# Analog.net
KiCad netlist of a schematic drawn in Altium Designer
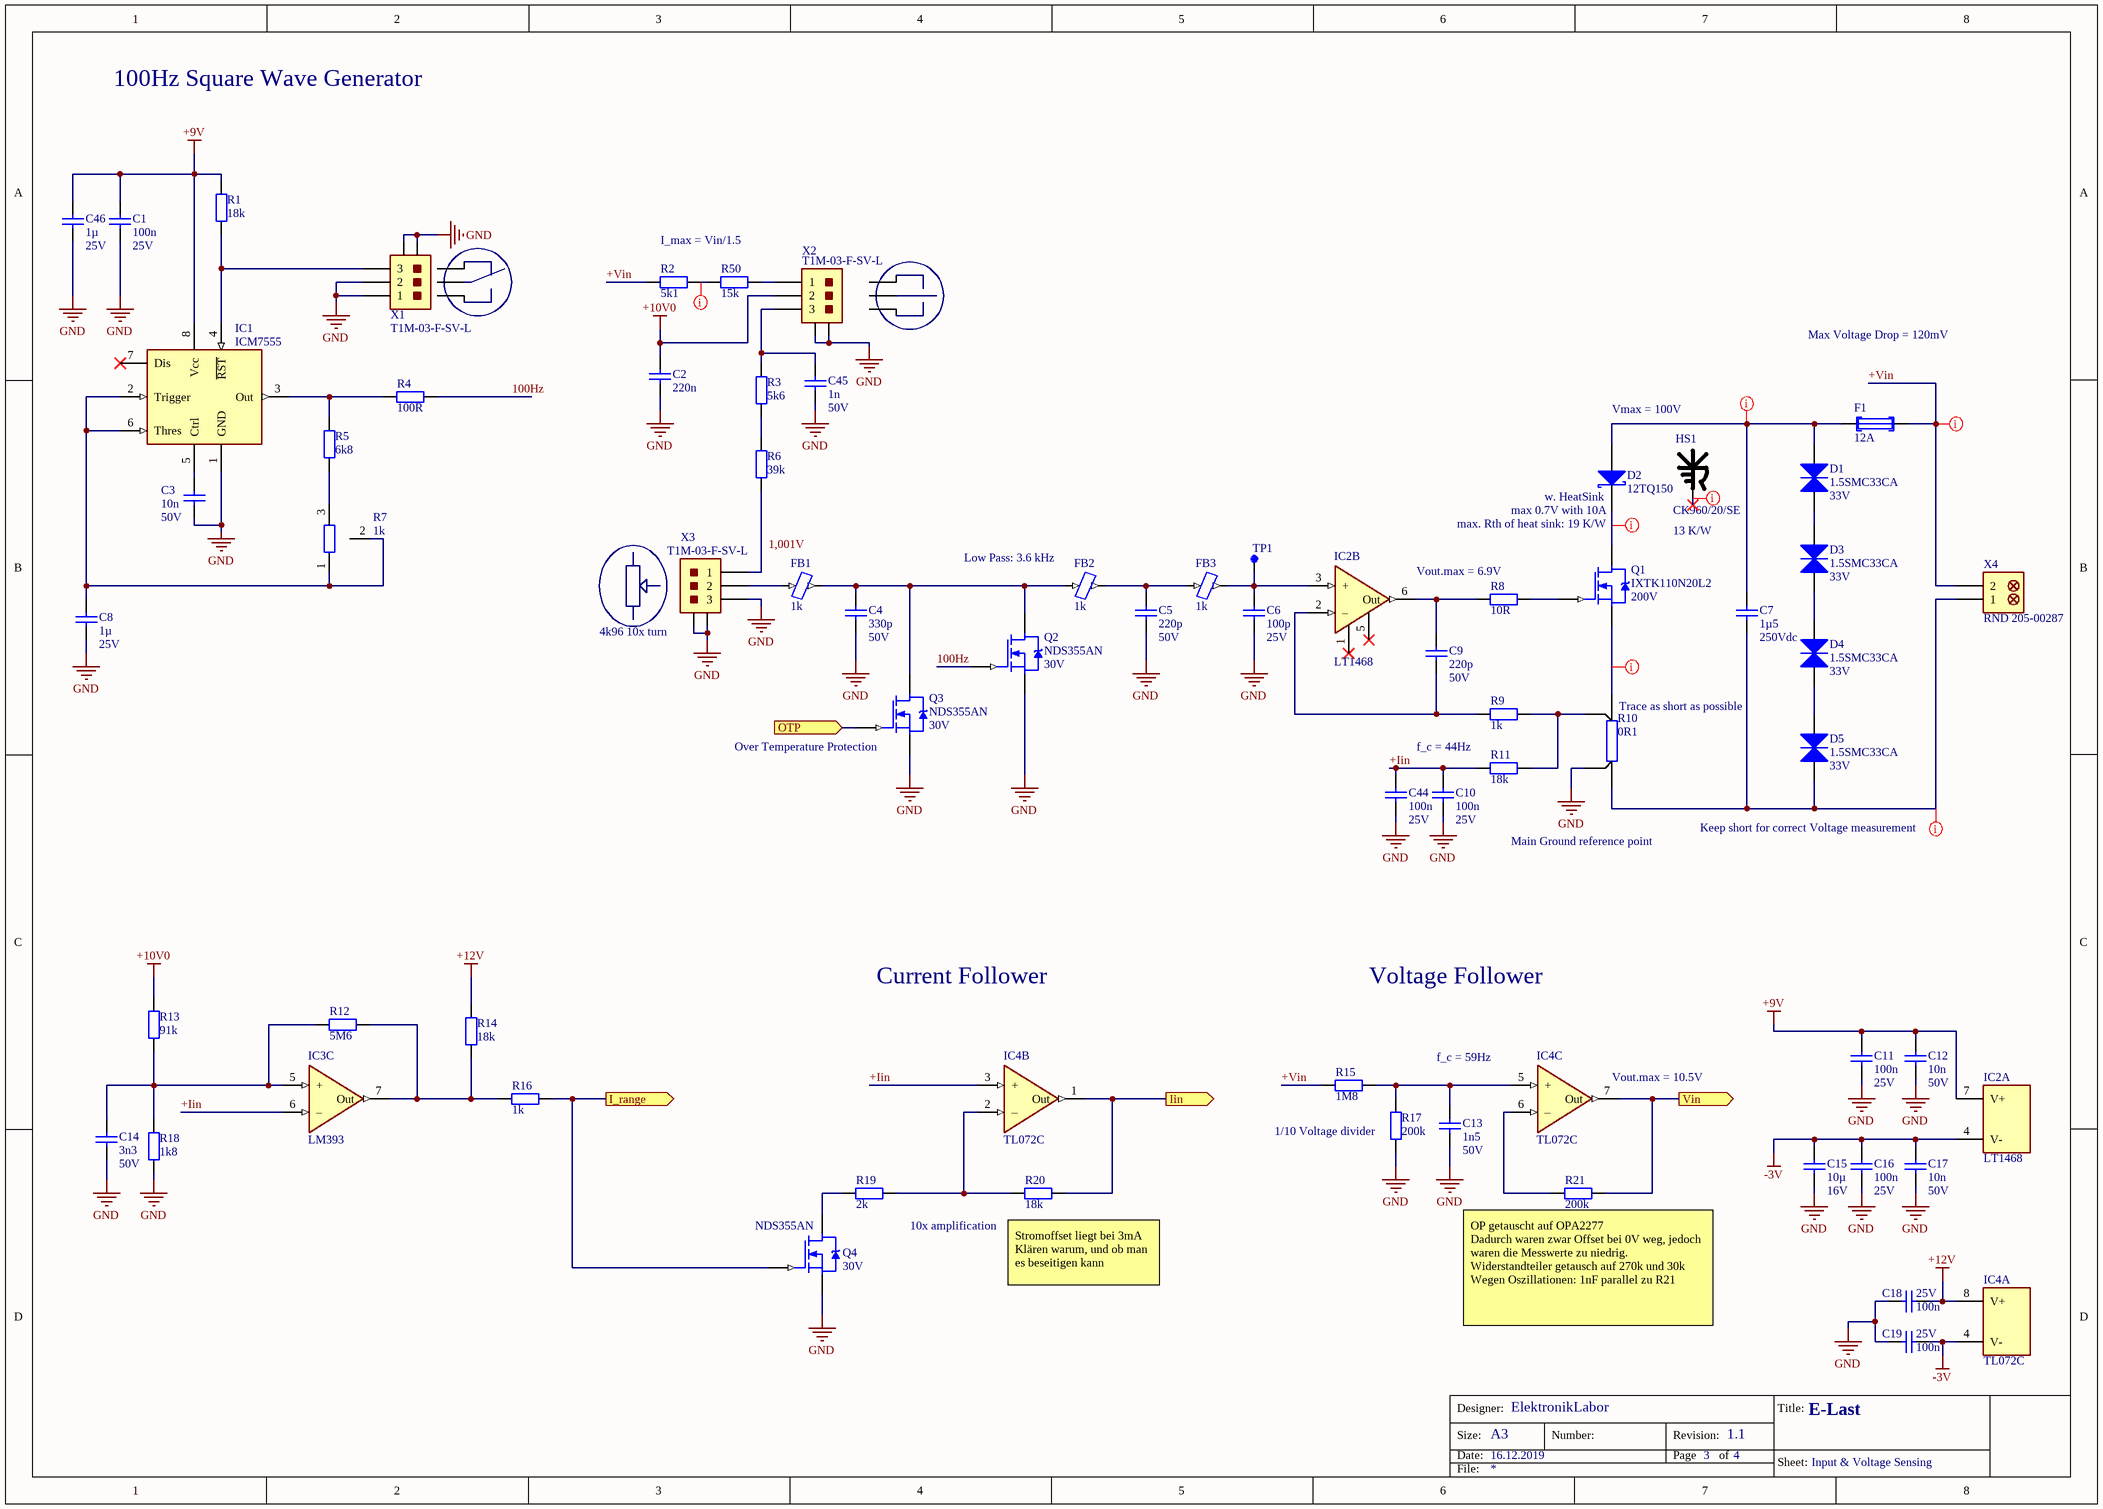
[diagram p0: Analog.SchDoc]

(export (version "E")
  (design (tool "Eeschema 10.0.6"))
  (components
    (comp (ref "C1")
      (value "100n")
      (footprint "C_0805")
      (description "Cap Ceramic 0805 100n 25V")
      (fields (field (name "MANUFACTURER") "generic") (field (name "VOLTAGE") "25V"))
      (libsource (lib "SchLibrary") (part "C-Cer 0805 100n"))
    )
    (comp (ref "C2")
      (value "220n")
      (footprint "C_0805")
      (description "Cap Ceramic 0805 220n 50V")
      (fields (field (name "MANUFACTURER") "generic") (field (name "VOLTAGE") "50V"))
      (libsource (lib "SchLibrary") (part "C-Cer 0805 220n"))
    )
    (comp (ref "C3")
      (value "10n")
      (footprint "C_0805")
      (description "Cap Ceramic 0805 10n 50V")
      (fields (field (name "MANUFACTURER") "generic") (field (name "VOLTAGE") "50V"))
      (libsource (lib "SchLibrary") (part "C-Cer 0805 10n"))
    )
    (comp (ref "C4")
      (value "330p")
      (footprint "C_0805")
      (description "Cap Ceramic 0805 330p 50V")
      (fields (field (name "MANUFACTURER") "generic") (field (name "VOLTAGE") "50V"))
      (libsource (lib "CustomLib") (part "C-Cer 0805 330p"))
    )
    (comp (ref "C5")
      (value "220p")
      (footprint "C_0805")
      (description "Cap Ceramic 0805 220p 50V")
      (fields (field (name "MANUFACTURER") "generic") (field (name "VOLTAGE") "50V"))
      (libsource (lib "CustomLib") (part "C-Cer 0805 220p"))
    )
    (comp (ref "C6")
      (value "100p")
      (footprint "C_0805")
      (description "Cap Ceramic 0805 100p 50V")
      (fields (field (name "MANUFACTURER") "generic") (field (name "VOLTAGE") "25V"))
      (libsource (lib "CustomLib") (part "C-Cer 0805 100p"))
    )
    (comp (ref "C7")
      (value "1µ5")
      (footprint "Cap Film 15mm THT")
      (description "Cap Film 1µ5 250V 15mm")
      (fields
        (field (name "MANUFACTURER") "Panasonic")
        (field (name "PARTNUMBER") "ECQE2155KF")
        (field (name "VOLTAGE") "250Vdc")
      )
      (libsource (lib "CustomLib") (part "Cap-Film 1µ5 250V 15mm"))
    )
    (comp (ref "C8")
      (value "1µ")
      (footprint "C_0805")
      (description "Cap Ceramic 0805 1µ 25V")
      (fields
        (field (name "MANUFACTURER") "Samsung")
        (field (name "PARTNUMBER") "CL21B105KAFNNNE")
        (field (name "VOLTAGE") "25V")
      )
      (libsource (lib "SchLibrary") (part "C-Cer 0805 1µ"))
    )
    (comp (ref "C9")
      (value "220p")
      (footprint "C_0805")
      (description "Cap Ceramic 0805 220p 50V")
      (fields (field (name "MANUFACTURER") "generic") (field (name "VOLTAGE") "50V"))
      (libsource (lib "CustomLib") (part "C-Cer 0805 220p"))
    )
    (comp (ref "C10")
      (value "100n")
      (footprint "C_0805")
      (description "Cap Ceramic 0805 100n 25V")
      (fields (field (name "MANUFACTURER") "generic") (field (name "VOLTAGE") "25V"))
      (libsource (lib "SchLibrary") (part "C-Cer 0805 100n"))
    )
    (comp (ref "C11")
      (value "100n")
      (footprint "C_0805")
      (description "Cap Ceramic 0805 100n 25V")
      (fields (field (name "MANUFACTURER") "generic") (field (name "VOLTAGE") "25V"))
      (libsource (lib "SchLibrary") (part "C-Cer 0805 100n"))
    )
    (comp (ref "C12")
      (value "10n")
      (footprint "C_0805")
      (description "Cap Ceramic 0805 10n 50V")
      (fields (field (name "MANUFACTURER") "generic") (field (name "VOLTAGE") "50V"))
      (libsource (lib "SchLibrary") (part "C-Cer 0805 10n"))
    )
    (comp (ref "C13")
      (value "1n5")
      (footprint "C_0805")
      (description "Cap Ceramic 0805 1n5 50V")
      (fields (field (name "MANUFACTURER") "generic") (field (name "VOLTAGE") "50V"))
      (libsource (lib "CustomLib") (part "C-Cer 0805 1n5"))
    )
    (comp (ref "C14")
      (value "3n3")
      (footprint "C_0805")
      (description "Cap Ceramic 0805 3n3 50V")
      (fields (field (name "MANUFACTURER") "generic") (field (name "VOLTAGE") "50V"))
      (libsource (lib "CustomLib") (part "C-Cer 0805 3n3"))
    )
    (comp (ref "C15")
      (value "10µ")
      (footprint "C_1206")
      (description "Cap Ceramic 1206 10µ 16V")
      (fields
        (field (name "PARTNUMBER") "CL31B106MOHNNNE")
        (field (name "MANUFACTURER") "Samsung")
        (field (name "VOLTAGE") "16V")
      )
      (libsource (lib "CustomLib") (part "C-Cer 1206 16V 10µ"))
    )
    (comp (ref "C16")
      (value "100n")
      (footprint "C_0805")
      (description "Cap Ceramic 0805 100n 25V")
      (fields (field (name "MANUFACTURER") "generic") (field (name "VOLTAGE") "25V"))
      (libsource (lib "SchLibrary") (part "C-Cer 0805 100n"))
    )
    (comp (ref "C17")
      (value "10n")
      (footprint "C_0805")
      (description "Cap Ceramic 0805 10n 50V")
      (fields (field (name "MANUFACTURER") "generic") (field (name "VOLTAGE") "50V"))
      (libsource (lib "SchLibrary") (part "C-Cer 0805 10n"))
    )
    (comp (ref "C18")
      (value "100n")
      (footprint "C_0805")
      (description "Cap Ceramic 0805 100n 25V")
      (fields (field (name "MANUFACTURER") "generic") (field (name "VOLTAGE") "25V"))
      (libsource (lib "SchLibrary") (part "C-Cer 0805 100n"))
    )
    (comp (ref "C19")
      (value "100n")
      (footprint "C_0805")
      (description "Cap Ceramic 0805 100n 25V")
      (fields (field (name "MANUFACTURER") "generic") (field (name "VOLTAGE") "25V"))
      (libsource (lib "SchLibrary") (part "C-Cer 0805 100n"))
    )
    (comp (ref "C44")
      (value "100n")
      (footprint "C_0805")
      (description "Cap Ceramic 0805 100n 25V")
      (fields (field (name "MANUFACTURER") "generic") (field (name "VOLTAGE") "25V"))
      (libsource (lib "SchLibrary") (part "C-Cer 0805 100n"))
    )
    (comp (ref "C45")
      (value "1n")
      (footprint "C_0805")
      (description "Cap Ceramic 0805 1n 50V")
      (fields (field (name "MANUFACTURER") "generic") (field (name "VOLTAGE") "50V"))
      (libsource (lib "CustomLib") (part "C-Cer 0805 1n"))
    )
    (comp (ref "C46")
      (value "1µ")
      (footprint "C_0805")
      (description "Cap Ceramic 0805 1µ 25V")
      (fields
        (field (name "MANUFACTURER") "Samsung")
        (field (name "PARTNUMBER") "CL21B105KAFNNNE")
        (field (name "VOLTAGE") "25V")
      )
      (libsource (lib "SchLibrary") (part "C-Cer 0805 1µ"))
    )
    (comp (ref "D1")
      (value "1.5SMC33CA")
      (footprint "DO-214AB")
      (description "Diode, TVS, Bi, 33V, 33A, DO-214AB")
      (fields
        (field (name "MANUFACTURER") "Littelfuse")
        (field (name "VOLTAGE") "33V")
        (field (name "COMPONENTLINK1URL") "G:\\Daten\\Datenblätter\\Dioden\\1_5SMC_TVS.pdf")
      )
      (libsource (lib "CustomLib") (part "Diode 1.5SMC33CA"))
    )
    (comp (ref "D2")
      (value "12TQ150")
      (footprint "TO-220-2 Vertical")
      (description "Diode Schottky, 150V, 15A, TO-220-2")
      (fields
        (field (name "MANUFACTURER") "SMC")
        (field (name "VOLTAGE") "150V")
        (field (name "COMPONENTLINK1URL") "G:\\Daten\\Datenblätter\\Dioden\\12TQ150.pdf")
      )
      (libsource (lib "SchLibrary") (part "Diode Schottky 15A"))
    )
    (comp (ref "D3")
      (value "1.5SMC33CA")
      (footprint "DO-214AB")
      (description "Diode, TVS, Bi, 33V, 33A, DO-214AB")
      (fields
        (field (name "MANUFACTURER") "Littelfuse")
        (field (name "VOLTAGE") "33V")
        (field (name "COMPONENTLINK1URL") "G:\\Daten\\Datenblätter\\Dioden\\1_5SMC_TVS.pdf")
      )
      (libsource (lib "CustomLib") (part "Diode 1.5SMC33CA"))
    )
    (comp (ref "D4")
      (value "1.5SMC33CA")
      (footprint "DO-214AB")
      (description "Diode, TVS, Bi, 33V, 33A, DO-214AB")
      (fields
        (field (name "MANUFACTURER") "Littelfuse")
        (field (name "VOLTAGE") "33V")
        (field (name "COMPONENTLINK1URL") "G:\\Daten\\Datenblätter\\Dioden\\1_5SMC_TVS.pdf")
      )
      (libsource (lib "CustomLib") (part "Diode 1.5SMC33CA"))
    )
    (comp (ref "D5")
      (value "1.5SMC33CA")
      (footprint "DO-214AB")
      (description "Diode, TVS, Bi, 33V, 33A, DO-214AB")
      (fields
        (field (name "MANUFACTURER") "Littelfuse")
        (field (name "VOLTAGE") "33V")
        (field (name "COMPONENTLINK1URL") "G:\\Daten\\Datenblätter\\Dioden\\1_5SMC_TVS.pdf")
      )
      (libsource (lib "CustomLib") (part "Diode 1.5SMC33CA"))
    )
    (comp (ref "F1")
      (value "12A")
      (footprint "Fuse w Holder 5x20mm 25mm")
      (description "Fuse w Holder 5x20mm 25mm 12A THT")
      (fields
        (field (name "MANUFACTURER") "Schurter")
        (field (name "PARTNUMBER") "0031.8211")
        (field (name "COMPONENTLINK1URL") "G:\\Daten\\Datenblätter\\Sicherungen\\Halter_15x20mm_Schurter_0031.82x1.pdf")
      )
      (libsource (lib "SchLibrary") (part "Fuse w Holder 0031.8211 12A"))
    )
    (comp (ref "FB1")
      (value "1k")
      (footprint "Ferrite 0805")
      (description "Ferrite Bead 0805 1k 100MHz")
      (fields
        (field (name "MANUFACTURER") "Murata")
        (field (name "PARTNUMBER") "BLM21AG102SN1")
        (field (name "COMPONENTLINK1URL") "G:\\Daten\\Datenblätter\\Ferrite\\BLM21AG102SN1.pdf")
      )
      (libsource (lib "SchLibrary") (part "Ferrite Bead BLM21AG102SN1"))
    )
    (comp (ref "FB2")
      (value "1k")
      (footprint "Ferrite 0805")
      (description "Ferrite Bead 0805 1k 100MHz")
      (fields
        (field (name "MANUFACTURER") "Murata")
        (field (name "PARTNUMBER") "BLM21AG102SN1")
        (field (name "COMPONENTLINK1URL") "G:\\Daten\\Datenblätter\\Ferrite\\BLM21AG102SN1.pdf")
      )
      (libsource (lib "SchLibrary") (part "Ferrite Bead BLM21AG102SN1"))
    )
    (comp (ref "FB3")
      (value "1k")
      (footprint "Ferrite 0805")
      (description "Ferrite Bead 0805 1k 100MHz")
      (fields
        (field (name "MANUFACTURER") "Murata")
        (field (name "PARTNUMBER") "BLM21AG102SN1")
        (field (name "COMPONENTLINK1URL") "G:\\Daten\\Datenblätter\\Ferrite\\BLM21AG102SN1.pdf")
      )
      (libsource (lib "SchLibrary") (part "Ferrite Bead BLM21AG102SN1"))
    )
    (comp (ref "HS1")
      (value "CK960/20/SE")
      (footprint "Mech Heat Sink CK960/20/SE")
      (description "Mech Heat Sink CK960/20/SE TO-220; Unfertig")
      (fields
        (field (name "MANUFACTURER") "Alutronic")
        (field (name "COMPONENTLINK1URL") "G:\\Daten\\Datenblätter\\Kühlkörper\\CK960-20-SE.pdf")
      )
      (libsource (lib "CustomLib") (part "Mech Heat Sink CK960/20/SE"))
    )
    (comp (ref "IC1")
      (value "ICM7555")
      (footprint "SOIC8_N")
      (description "Timer ICM7555 8-SOIC")
      (fields
        (field (name "MANUFACTURER") "Intersil")
        (field (name "PARTNUMBER") "ICM7555IBA")
        (field (name "COMPONENTLINK1URL") "G:\\Daten\\Datenblätter\\Timer\\ICM755IBA.pdf")
      )
      (libsource (lib "CustomLib") (part "Timer ICM7555IBA"))
    )
    (comp (ref "IC2")
      (value "LT1468")
      (footprint "SOIC8_N")
      (description "OpAmp LT1468 1x 90MHz")
      (fields
        (field (name "MANUFACTURER") "Linear Technology")
        (field (name "PARTNUMBER") "LT1468CS8")
        (field (name "COMPONENTLINK1URL") "G:\\Daten\\Datenblätter\\Operationsverstärker\\LT1468.pdf")
      )
      (libsource (lib "SchLibrary") (part "LT1468"))
    )
    (comp (ref "IC3")
      (value "LM393")
      (footprint "SOIC8_N")
      (description "Comparator LM393DT 2x")
      (fields
        (field (name "MANUFACTURER") "ST")
        (field (name "PARTNUMBER") "LM393DT")
        (field (name "COMPONENTLINK1URL") "G:\\Daten\\Datenblätter\\Komparatoren\\ST_LM393.pdf")
      )
      (libsource (lib "SchLibrary") (part "LM393DT"))
    )
    (comp (ref "IC4")
      (value "TL072C")
      (footprint "SOIC8_N")
      (description "OpAmp TL072CD 2x JFET 3MHz")
      (fields
        (field (name "MANUFACTURER") "Texas Instruments")
        (field (name "PARTNUMBER") "TL072CD")
        (field (name "COMPONENTLINK1URL") "G:\\Daten\\Datenblätter\\Operationsverstärker\\TL072C.pdf")
      )
      (libsource (lib "SchLibrary") (part "TL072C"))
    )
    (comp (ref "Q1")
      (value "IXTK110N20L2")
      (footprint "TO-264-3 vertical")
      (description "Transistor n-MOS, TO-264, 200V, THT")
      (fields
        (field (name "MANUFACTURER") "IXYS")
        (field (name "VOLTAGE") "200V")
        (field (name "COMPONENTLINK1URL") "G:\\Daten\\Datenblätter\\Transistoren\\nMOS_IXTK110N20L2.pdf")
      )
      (libsource (lib "SchLibrary") (part "Transistor n-MOS IXTK110N20L2"))
    )
    (comp (ref "Q2")
      (value "NDS355AN")
      (footprint "SOT23_N - n-MOS")
      (description "Transistor n-MOS SOT-23 30V Vgs=20V")
      (fields
        (field (name "MANUFACTURER") "ON Semiconductor")
        (field (name "VOLTAGE") "30V")
        (field (name "COMPONENTLINK1URL") "G:\\Daten\\Datenblätter\\Transistoren\\nMOS_NDS355AN.pdf")
      )
      (libsource (lib "CustomLib") (part "Transistor n-MOS NDS355AN"))
    )
    (comp (ref "Q3")
      (value "NDS355AN")
      (footprint "SOT23_N - n-MOS")
      (description "Transistor n-MOS SOT-23 30V Vgs=20V")
      (fields
        (field (name "MANUFACTURER") "ON Semiconductor")
        (field (name "VOLTAGE") "30V")
        (field (name "COMPONENTLINK1URL") "G:\\Daten\\Datenblätter\\Transistoren\\nMOS_NDS355AN.pdf")
      )
      (libsource (lib "CustomLib") (part "Transistor n-MOS NDS355AN"))
    )
    (comp (ref "Q4")
      (value "NDS355AN")
      (footprint "SOT23_N - n-MOS")
      (description "Transistor n-MOS SOT-23 30V Vgs=20V")
      (fields
        (field (name "MANUFACTURER") "ON Semiconductor")
        (field (name "VOLTAGE") "30V")
        (field (name "COMPONENTLINK1URL") "G:\\Daten\\Datenblätter\\Transistoren\\nMOS_NDS355AN.pdf")
      )
      (libsource (lib "SchLibrary") (part "Transistor n-MOS NDS355AN"))
    )
    (comp (ref "R1")
      (value "18k")
      (footprint "Res 0805")
      (description "Resistor 0805 18k")
      (fields (field (name "MANUFACTURER") "generic") (field (name "POWER") "0.125W"))
      (libsource (lib "CustomLib") (part "Res 0805 18k"))
    )
    (comp (ref "R2")
      (value "5k1")
      (footprint "Res 0805")
      (description "Resistor 0805 5k1")
      (fields (field (name "MANUFACTURER") "generic") (field (name "POWER") "0.125W"))
      (libsource (lib "CustomLib") (part "Res 0805 5k1"))
    )
    (comp (ref "R3")
      (value "5k6")
      (footprint "Res 0805")
      (description "Resistor 0805 5k6")
      (fields (field (name "MANUFACTURER") "generic") (field (name "POWER") "0.125W"))
      (libsource (lib "CustomLib") (part "Res 0805 5k6"))
    )
    (comp (ref "R4")
      (value "100R")
      (footprint "Res 0805")
      (description "Resistor 0805 100R")
      (fields (field (name "MANUFACTURER") "generic") (field (name "POWER") "0.125W"))
      (libsource (lib "SchLibrary") (part "Res 0805 100R"))
    )
    (comp (ref "R5")
      (value "6k8")
      (footprint "Res 0805")
      (description "Resistor 0805 6k8")
      (fields (field (name "MANUFACTURER") "generic") (field (name "POWER") "0.125W"))
      (libsource (lib "SchLibrary") (part "Res 0805 6k8"))
    )
    (comp (ref "R6")
      (value "39k")
      (footprint "Res 0805")
      (description "Resistor 0805 39k")
      (fields (field (name "MANUFACTURER") "generic") (field (name "POWER") "0.125W"))
      (libsource (lib "CustomLib") (part "Res 0805 39k"))
    )
    (comp (ref "R7")
      (value "1k")
      (footprint "Poti 3296Y")
      (description "Pot 1k THT 30 turns")
      (fields
        (field (name "MANUFACTURER") "Suntan")
        (field (name "PARTNUMBER") "TSR-3296-Y-102-R")
        (field (name "COMPONENTLINK1URL") "G:\\Daten\\Datenblätter\\Potentiometer\\TSR-3296.pdf")
      )
      (libsource (lib "SchLibrary") (part "Pot 1k THT"))
    )
    (comp (ref "R8")
      (value "10R")
      (footprint "Res 0805")
      (description "Resistor 0805 10R")
      (fields (field (name "MANUFACTURER") "generic") (field (name "POWER") "0.125W"))
      (libsource (lib "SchLibrary") (part "Res 0805 10R"))
    )
    (comp (ref "R9")
      (value "1k")
      (footprint "Res 0805")
      (description "Resistor 0805 1k")
      (fields (field (name "MANUFACTURER") "generic") (field (name "POWER") "0.125W"))
      (libsource (lib "SchLibrary") (part "Res 0805 1k"))
    )
    (comp (ref "R10")
      (value "0R1")
      (footprint "Res 4-SIL")
      (description "Resistor 4-SIL 0R1 0.5% 40W")
      (fields
        (field (name "MANUFACTURER") "Riedon")
        (field (name "PARTNUMBER") "PCS-0R1D1")
        (field (name "COMPONENTLINK1URL") "G:\\Daten\\Datenblätter\\Widerstände\\Riedon_PCS-PBV.pdf")
      )
      (libsource (lib "SchLibrary") (part "Res 4-SIL 0R1"))
    )
    (comp (ref "R11")
      (value "18k")
      (footprint "Res 0805")
      (description "Resistor 0805 18k")
      (fields (field (name "MANUFACTURER") "generic") (field (name "POWER") "0.125W"))
      (libsource (lib "") (part "Res 0805 18k_1"))
    )
    (comp (ref "R12")
      (value "5M6")
      (footprint "Res 0805")
      (description "Resistor 0805 5M6")
      (fields (field (name "MANUFACTURER") "generic") (field (name "POWER") "0.125W"))
      (libsource (lib "SchLibrary") (part "Res 0805 5M6"))
    )
    (comp (ref "R13")
      (value "91k")
      (footprint "Res 0805")
      (description "Resistor 0805 91k")
      (fields (field (name "MANUFACTURER") "generic") (field (name "POWER") "0.125W"))
      (libsource (lib "SchLibrary") (part "Res 0805 91k"))
    )
    (comp (ref "R14")
      (value "18k")
      (footprint "Res 0805")
      (description "Resistor 0805 18k")
      (fields (field (name "MANUFACTURER") "generic") (field (name "POWER") "0.125W"))
      (libsource (lib "SchLibrary") (part "Res 0805 18k"))
    )
    (comp (ref "R15")
      (value "1M8")
      (footprint "Res 0805")
      (description "Resistor 0805 1M8")
      (fields (field (name "MANUFACTURER") "generic") (field (name "POWER") "0.125W"))
      (libsource (lib "SchLibrary") (part "Res 0805 1M8"))
    )
    (comp (ref "R16")
      (value "1k")
      (footprint "Res 0805")
      (description "Resistor 0805 1k")
      (fields (field (name "MANUFACTURER") "generic") (field (name "POWER") "0.125W"))
      (libsource (lib "SchLibrary") (part "Res 0805 1k"))
    )
    (comp (ref "R17")
      (value "200k")
      (footprint "Res 0805")
      (description "Resistor 0805 200k")
      (fields (field (name "MANUFACTURER") "generic") (field (name "POWER") "0.125W"))
      (libsource (lib "") (part "Res 0805 200k_1"))
    )
    (comp (ref "R18")
      (value "1k8")
      (footprint "Res 0805")
      (description "Resistor 0805 1k8")
      (fields (field (name "MANUFACTURER") "generic") (field (name "POWER") "0.125W"))
      (libsource (lib "SchLibrary") (part "Res 0805 1k8"))
    )
    (comp (ref "R19")
      (value "2k")
      (footprint "Res 0805")
      (description "Resistor 0805 2k")
      (fields (field (name "MANUFACTURER") "generic") (field (name "POWER") "0.125W"))
      (libsource (lib "SchLibrary") (part "Res 0805 2k"))
    )
    (comp (ref "R20")
      (value "18k")
      (footprint "Res 0805")
      (description "Resistor 0805 18k")
      (fields (field (name "MANUFACTURER") "generic") (field (name "POWER") "0.125W"))
      (libsource (lib "") (part "Res 0805 18k_1"))
    )
    (comp (ref "R21")
      (value "200k")
      (footprint "Res 0805")
      (description "Resistor 0805 200k")
      (fields (field (name "MANUFACTURER") "generic") (field (name "POWER") "0.125W"))
      (libsource (lib "SchLibrary") (part "Res 0805 200k"))
    )
    (comp (ref "R50")
      (value "15k")
      (footprint "Res 0805")
      (description "Resistor 0805 15k")
      (fields (field (name "MANUFACTURER") "generic") (field (name "POWER") "0.125W"))
      (libsource (lib "CustomLib") (part "Res 0805 15k"))
    )
    (comp (ref "TP1")
      (value "*")
      (footprint "Test Point SMD Rnd 1mm")
      (description "Test Point")
      (libsource (lib "CustomLib") (part "Test Point"))
    )
    (comp (ref "X1")
      (value "T1M-03-F-SV-L")
      (footprint "T1M-03-XX-S-V")
      (description "Connector, Male, Vertical, 3-Pin, 1mm, SMD")
      (fields
        (field (name "MANUFACTURER") "SAMTEC")
        (field (name "MATINGPARTNUMBER") "S1SS-03-L")
        (field (name "COMPONENTLINK1URL") "G:\\Daten\\Datenblätter\\Steckverbinder\\T1M-Single-Row.pdf")
      )
      (libsource (lib "") (part "Con Male 3-Pin_2"))
    )
    (comp (ref "X2")
      (value "T1M-03-F-SV-L")
      (footprint "T1M-03-XX-S-V")
      (description "Connector, Male, Vertical, 3-Pin, 1mm, SMD")
      (fields
        (field (name "MANUFACTURER") "SAMTEC")
        (field (name "MATINGPARTNUMBER") "S1SS-03-L")
        (field (name "COMPONENTLINK1URL") "G:\\Daten\\Datenblätter\\Steckverbinder\\T1M-Single-Row.pdf")
      )
      (libsource (lib "SchLibrary") (part "Con Male 3-Pin"))
    )
    (comp (ref "X3")
      (value "T1M-03-F-SV-L")
      (footprint "T1M-03-XX-S-V")
      (description "Connector, Male, Vertical, 3-Pin, 1mm, SMD")
      (fields
        (field (name "MANUFACTURER") "SAMTEC")
        (field (name "MATINGPARTNUMBER") "S1SS-03-L")
        (field (name "COMPONENTLINK1URL") "G:\\Daten\\Datenblätter\\Steckverbinder\\T1M-Single-Row.pdf")
      )
      (libsource (lib "") (part "Con Male 3-Pin_1"))
    )
    (comp (ref "X4")
      (value "RND 205-00287")
      (footprint "TRMNL 5.08mm 2x")
      (description "Terminal, 2-Pin, 5.08mm, THT")
      (fields
        (field (name "MANUFACTURER") "RND connect")
        (field (name "COMPONENTLINK2URL") "G:\\Daten\\Datenblätter\\Verbinder\\Terminal_RND_205-00287.pdf")
      )
      (libsource (lib "SchLibrary") (part "Termial 2pin 5.08mm"))
    )
  )
  (nets
    (net (code "1") (name "+9V") (class "Default")
      (node (ref "C1") (pin "1") (pinfunction "1_1") (pintype "passive"))
      (node (ref "C11") (pin "1") (pinfunction "1_1") (pintype "passive"))
      (node (ref "C12") (pin "1") (pinfunction "1_1") (pintype "passive"))
      (node (ref "C46") (pin "1") (pinfunction "1_1") (pintype "passive"))
      (node (ref "IC1") (pin "8") (pinfunction "Vcc_8") (pintype "power_in"))
      (node (ref "IC2") (pin "7") (pinfunction "V+_7") (pintype "power_in"))
      (node (ref "R1") (pin "1") (pinfunction "1_1") (pintype "passive"))
    )
    (net (code "2") (name "+10V0") (class "Default")
      (node (ref "C2") (pin "1") (pinfunction "1_1") (pintype "passive"))
      (node (ref "R13") (pin "1") (pinfunction "1_1") (pintype "passive"))
      (node (ref "X2") (pin "2") (pinfunction "2_2") (pintype "passive"))
    )
    (net (code "3") (name "+12V") (class "Default")
      (node (ref "C18") (pin "2") (pinfunction "2_2") (pintype "passive"))
      (node (ref "IC4") (pin "8") (pinfunction "V+_8") (pintype "power_in"))
      (node (ref "R14") (pin "1") (pinfunction "1_1") (pintype "passive"))
    )
    (net (code "4") (name "-3V") (class "Default")
      (node (ref "C15") (pin "1") (pinfunction "1_1") (pintype "passive"))
      (node (ref "C16") (pin "1") (pinfunction "1_1") (pintype "passive"))
      (node (ref "C17") (pin "1") (pinfunction "1_1") (pintype "passive"))
      (node (ref "C19") (pin "1") (pinfunction "1_1") (pintype "passive"))
      (node (ref "IC2") (pin "4") (pinfunction "V-_4") (pintype "power_in"))
      (node (ref "IC4") (pin "4") (pinfunction "V-_4") (pintype "power_in"))
    )
    (net (code "5") (name "/+Iin") (class "Default")
      (node (ref "C10") (pin "1") (pinfunction "1_1") (pintype "passive"))
      (node (ref "C44") (pin "1") (pinfunction "1_1") (pintype "passive"))
      (node (ref "IC3") (pin "6") (pinfunction "–_6") (pintype "input"))
      (node (ref "IC4") (pin "3") (pinfunction "+_3") (pintype "input"))
      (node (ref "R11") (pin "1") (pinfunction "1_1") (pintype "passive"))
    )
    (net (code "6") (name "/+Vin") (class "Default")
      (node (ref "F1") (pin "2") (pinfunction "2_2") (pintype "passive"))
      (node (ref "R15") (pin "1") (pinfunction "1_1") (pintype "passive"))
      (node (ref "R2") (pin "1") (pinfunction "1_1") (pintype "passive"))
      (node (ref "X4") (pin "2") (pinfunction "2_2") (pintype "passive"))
    )
    (net (code "7") (name "/100Hz") (class "Default")
      (node (ref "Q2") (pin "1") (pinfunction "G_1") (pintype "input"))
      (node (ref "R4") (pin "2") (pinfunction "2_2") (pintype "passive"))
    )
    (net (code "8") (name "/I_range") (class "Default")
      (node (ref "Q4") (pin "1") (pinfunction "G_1") (pintype "input"))
      (node (ref "R16") (pin "2") (pinfunction "2_2") (pintype "passive"))
    )
    (net (code "9") (name "/Iin") (class "Default")
      (node (ref "IC4") (pin "1") (pinfunction "Out_1") (pintype "output"))
      (node (ref "R20") (pin "2") (pinfunction "2_2") (pintype "passive"))
    )
    (net (code "10") (name "/OTP") (class "Default")
      (node (ref "Q3") (pin "1") (pinfunction "G_1") (pintype "input"))
    )
    (net (code "11") (name "/Vin") (class "Default")
      (node (ref "IC4") (pin "7") (pinfunction "Out_7") (pintype "output"))
      (node (ref "R21") (pin "2") (pinfunction "2_2") (pintype "passive"))
    )
    (net (code "12") (name "GND") (class "Default")
      (node (ref "C1") (pin "2") (pinfunction "2_2") (pintype "passive"))
      (node (ref "C10") (pin "2") (pinfunction "2_2") (pintype "passive"))
      (node (ref "C11") (pin "2") (pinfunction "2_2") (pintype "passive"))
      (node (ref "C12") (pin "2") (pinfunction "2_2") (pintype "passive"))
      (node (ref "C13") (pin "2") (pinfunction "2_2") (pintype "passive"))
      (node (ref "C14") (pin "2") (pinfunction "2_2") (pintype "passive"))
      (node (ref "C15") (pin "2") (pinfunction "2_2") (pintype "passive"))
      (node (ref "C16") (pin "2") (pinfunction "2_2") (pintype "passive"))
      (node (ref "C17") (pin "2") (pinfunction "2_2") (pintype "passive"))
      (node (ref "C18") (pin "1") (pinfunction "1_1") (pintype "passive"))
      (node (ref "C19") (pin "2") (pinfunction "2_2") (pintype "passive"))
      (node (ref "C2") (pin "2") (pinfunction "2_2") (pintype "passive"))
      (node (ref "C3") (pin "2") (pinfunction "2_2") (pintype "passive"))
      (node (ref "C4") (pin "2") (pinfunction "2_2") (pintype "passive"))
      (node (ref "C44") (pin "2") (pinfunction "2_2") (pintype "passive"))
      (node (ref "C45") (pin "2") (pinfunction "2_2") (pintype "passive"))
      (node (ref "C46") (pin "2") (pinfunction "2_2") (pintype "passive"))
      (node (ref "C5") (pin "2") (pinfunction "2_2") (pintype "passive"))
      (node (ref "C6") (pin "2") (pinfunction "2_2") (pintype "passive"))
      (node (ref "C8") (pin "2") (pinfunction "2_2") (pintype "passive"))
      (node (ref "IC1") (pin "1") (pinfunction "GND_1") (pintype "passive"))
      (node (ref "Q2") (pin "2") (pinfunction "S_2") (pintype "passive"))
      (node (ref "Q3") (pin "2") (pinfunction "S_2") (pintype "passive"))
      (node (ref "Q4") (pin "2") (pinfunction "S_2") (pintype "passive"))
      (node (ref "R10") (pin "3") (pinfunction "3_3") (pintype "passive"))
      (node (ref "R17") (pin "2") (pinfunction "2_2") (pintype "passive"))
      (node (ref "R18") (pin "2") (pinfunction "2_2") (pintype "passive"))
      (node (ref "X1") (pin "1") (pinfunction "1_1") (pintype "passive"))
      (node (ref "X1") (pin "2") (pinfunction "2_2") (pintype "passive"))
      (node (ref "X1") (pin "4") (pinfunction "CASE_4") (pintype "passive"))
      (node (ref "X1") (pin "5") (pinfunction "CASE_5") (pintype "passive"))
      (node (ref "X2") (pin "4") (pinfunction "CASE_4") (pintype "passive"))
      (node (ref "X2") (pin "5") (pinfunction "CASE_5") (pintype "passive"))
      (node (ref "X3") (pin "3") (pinfunction "3_3") (pintype "passive"))
      (node (ref "X3") (pin "4") (pinfunction "CASE_4") (pintype "passive"))
      (node (ref "X3") (pin "5") (pinfunction "CASE_5") (pintype "passive"))
    )
    (net (code "13") (name "Net-(C5-Pad1)") (class "Default")
      (node (ref "C5") (pin "1") (pinfunction "1_1") (pintype "passive"))
      (node (ref "FB2") (pin "2") (pinfunction "2_2") (pintype "output"))
      (node (ref "FB3") (pin "1") (pinfunction "1_1") (pintype "input"))
    )
    (net (code "14") (name "Net-(C7-Pad2)") (class "Default")
      (node (ref "C7") (pin "2") (pinfunction "2_2") (pintype "passive"))
      (node (ref "D5") (pin "2") (pinfunction "2_2") (pintype "passive"))
      (node (ref "R10") (pin "4") (pinfunction "4_4") (pintype "passive"))
      (node (ref "X4") (pin "1") (pinfunction "1_1") (pintype "passive"))
    )
    (net (code "15") (name "Net-(C45-Pad1)") (class "Default")
      (node (ref "C45") (pin "1") (pinfunction "1_1") (pintype "passive"))
      (node (ref "R3") (pin "1") (pinfunction "1_1") (pintype "passive"))
      (node (ref "X2") (pin "3") (pinfunction "3_3") (pintype "passive"))
    )
    (net (code "16") (name "Net-(D1-Pad2)") (class "Default")
      (node (ref "D1") (pin "2") (pinfunction "2_2") (pintype "passive"))
      (node (ref "D3") (pin "1") (pinfunction "1_1") (pintype "passive"))
    )
    (net (code "17") (name "Net-(D2-A)") (class "Default")
      (node (ref "C7") (pin "1") (pinfunction "1_1") (pintype "passive"))
      (node (ref "D1") (pin "1") (pinfunction "1_1") (pintype "passive"))
      (node (ref "D2") (pin "2") (pinfunction "A_2") (pintype "passive"))
      (node (ref "F1") (pin "1") (pinfunction "1_1") (pintype "passive"))
    )
    (net (code "18") (name "Net-(D2-K)") (class "Default")
      (node (ref "D2") (pin "1") (pinfunction "K_1") (pintype "passive"))
      (node (ref "Q1") (pin "2") (pinfunction "D_2") (pintype "passive"))
    )
    (net (code "19") (name "Net-(D3-Pad2)") (class "Default")
      (node (ref "D3") (pin "2") (pinfunction "2_2") (pintype "passive"))
      (node (ref "D4") (pin "1") (pinfunction "1_1") (pintype "passive"))
    )
    (net (code "20") (name "Net-(D4-Pad2)") (class "Default")
      (node (ref "D4") (pin "2") (pinfunction "2_2") (pintype "passive"))
      (node (ref "D5") (pin "1") (pinfunction "1_1") (pintype "passive"))
    )
    (net (code "21") (name "Net-(FB1-Pad1)") (class "Default")
      (node (ref "FB1") (pin "1") (pinfunction "1_1") (pintype "input"))
      (node (ref "X3") (pin "2") (pinfunction "2_2") (pintype "passive"))
    )
    (net (code "22") (name "Net-(IC1-Ctrl)") (class "Default")
      (node (ref "C3") (pin "1") (pinfunction "1_1") (pintype "passive"))
      (node (ref "IC1") (pin "5") (pinfunction "Ctrl_5") (pintype "passive"))
    )
    (net (code "23") (name "Net-(IC1-Out)") (class "Default")
      (node (ref "IC1") (pin "3") (pinfunction "Out_3") (pintype "output"))
      (node (ref "R4") (pin "1") (pinfunction "1_1") (pintype "passive"))
      (node (ref "R5") (pin "1") (pinfunction "1_1") (pintype "passive"))
    )
    (net (code "24") (name "Net-(IC1-Thres)") (class "Default")
      (node (ref "C8") (pin "1") (pinfunction "1_1") (pintype "passive"))
      (node (ref "IC1") (pin "2") (pinfunction "Trigger_2") (pintype "input"))
      (node (ref "IC1") (pin "6") (pinfunction "Thres_6") (pintype "input"))
      (node (ref "R7") (pin "1") (pinfunction "1_1") (pintype "passive"))
      (node (ref "R7") (pin "2") (pinfunction "2_2") (pintype "passive"))
    )
    (net (code "25") (name "Net-(IC1-~{RST})") (class "Default")
      (node (ref "IC1") (pin "4") (pinfunction "~{RST}_4") (pintype "input"))
      (node (ref "R1") (pin "2") (pinfunction "2_2") (pintype "passive"))
      (node (ref "X1") (pin "3") (pinfunction "3_3") (pintype "passive"))
    )
    (net (code "26") (name "Net-(IC2B-+)") (class "Default")
      (node (ref "C6") (pin "1") (pinfunction "1_1") (pintype "passive"))
      (node (ref "FB3") (pin "2") (pinfunction "2_2") (pintype "output"))
      (node (ref "IC2") (pin "3") (pinfunction "+_3") (pintype "input"))
      (node (ref "TP1") (pin "1") (pinfunction "1_1") (pintype "passive"))
    )
    (net (code "27") (name "Net-(IC2B-Out)") (class "Default")
      (node (ref "C9") (pin "1") (pinfunction "1_1") (pintype "passive"))
      (node (ref "IC2") (pin "6") (pinfunction "Out_6") (pintype "output"))
      (node (ref "R8") (pin "1") (pinfunction "1_1") (pintype "passive"))
    )
    (net (code "28") (name "Net-(IC2B-–)") (class "Default")
      (node (ref "C9") (pin "2") (pinfunction "2_2") (pintype "passive"))
      (node (ref "IC2") (pin "2") (pinfunction "–_2") (pintype "input"))
      (node (ref "R9") (pin "1") (pinfunction "1_1") (pintype "passive"))
    )
    (net (code "29") (name "Net-(IC3C-+)") (class "Default")
      (node (ref "C14") (pin "1") (pinfunction "1_1") (pintype "passive"))
      (node (ref "IC3") (pin "5") (pinfunction "+_5") (pintype "input"))
      (node (ref "R12") (pin "1") (pinfunction "1_1") (pintype "passive"))
      (node (ref "R13") (pin "2") (pinfunction "2_2") (pintype "passive"))
      (node (ref "R18") (pin "1") (pinfunction "1_1") (pintype "passive"))
    )
    (net (code "30") (name "Net-(IC3C-Out)") (class "Default")
      (node (ref "IC3") (pin "7") (pinfunction "Out_7") (pintype "output"))
      (node (ref "R12") (pin "2") (pinfunction "2_2") (pintype "passive"))
      (node (ref "R14") (pin "2") (pinfunction "2_2") (pintype "passive"))
      (node (ref "R16") (pin "1") (pinfunction "1_1") (pintype "passive"))
    )
    (net (code "31") (name "Net-(IC4B-–)") (class "Default")
      (node (ref "IC4") (pin "2") (pinfunction "–_2") (pintype "input"))
      (node (ref "R19") (pin "2") (pinfunction "2_2") (pintype "passive"))
      (node (ref "R20") (pin "1") (pinfunction "1_1") (pintype "passive"))
    )
    (net (code "32") (name "Net-(IC4C-+)") (class "Default")
      (node (ref "C13") (pin "1") (pinfunction "1_1") (pintype "passive"))
      (node (ref "IC4") (pin "5") (pinfunction "+_5") (pintype "input"))
      (node (ref "R15") (pin "2") (pinfunction "2_2") (pintype "passive"))
      (node (ref "R17") (pin "1") (pinfunction "1_1") (pintype "passive"))
    )
    (net (code "33") (name "Net-(IC4C-–)") (class "Default")
      (node (ref "IC4") (pin "6") (pinfunction "–_6") (pintype "input"))
      (node (ref "R21") (pin "1") (pinfunction "1_1") (pintype "passive"))
    )
    (net (code "34") (name "Net-(Q1-G)") (class "Default")
      (node (ref "Q1") (pin "1") (pinfunction "G_1") (pintype "input"))
      (node (ref "R8") (pin "2") (pinfunction "2_2") (pintype "passive"))
    )
    (net (code "35") (name "Net-(Q1-S)") (class "Default")
      (node (ref "Q1") (pin "3") (pinfunction "S_3") (pintype "passive"))
      (node (ref "R10") (pin "1") (pinfunction "1_1") (pintype "passive"))
    )
    (net (code "36") (name "Net-(Q2-D)") (class "Default")
      (node (ref "C4") (pin "1") (pinfunction "1_1") (pintype "passive"))
      (node (ref "FB1") (pin "2") (pinfunction "2_2") (pintype "output"))
      (node (ref "FB2") (pin "1") (pinfunction "1_1") (pintype "input"))
      (node (ref "Q2") (pin "3") (pinfunction "D_3") (pintype "passive"))
      (node (ref "Q3") (pin "3") (pinfunction "D_3") (pintype "passive"))
    )
    (net (code "37") (name "Net-(Q4-D)") (class "Default")
      (node (ref "Q4") (pin "3") (pinfunction "D_3") (pintype "passive"))
      (node (ref "R19") (pin "1") (pinfunction "1_1") (pintype "passive"))
    )
    (net (code "38") (name "Net-(R2-Pad2)") (class "Default")
      (node (ref "R2") (pin "2") (pinfunction "2_2") (pintype "passive"))
      (node (ref "R50") (pin "1") (pinfunction "1_1") (pintype "passive"))
    )
    (net (code "39") (name "Net-(R3-Pad2)") (class "Default")
      (node (ref "R3") (pin "2") (pinfunction "2_2") (pintype "passive"))
      (node (ref "R6") (pin "1") (pinfunction "1_1") (pintype "passive"))
    )
    (net (code "40") (name "Net-(R5-Pad2)") (class "Default")
      (node (ref "R5") (pin "2") (pinfunction "2_2") (pintype "passive"))
      (node (ref "R7") (pin "3") (pinfunction "3_3") (pintype "passive"))
    )
    (net (code "41") (name "Net-(R6-Pad2)") (class "Default")
      (node (ref "R6") (pin "2") (pinfunction "2_2") (pintype "passive"))
      (node (ref "X3") (pin "1") (pinfunction "1_1") (pintype "passive"))
    )
    (net (code "42") (name "Net-(R10-Pad2)") (class "Default")
      (node (ref "R10") (pin "2") (pinfunction "2_2") (pintype "passive"))
      (node (ref "R11") (pin "2") (pinfunction "2_2") (pintype "passive"))
      (node (ref "R9") (pin "2") (pinfunction "2_2") (pintype "passive"))
    )
    (net (code "43") (name "Net-(R50-Pad2)") (class "Default")
      (node (ref "R50") (pin "2") (pinfunction "2_2") (pintype "passive"))
      (node (ref "X2") (pin "1") (pinfunction "1_1") (pintype "passive"))
    )
    (net (code "44") (name "unconnected-(HS1-Pad1)") (class "Default")
      (node (ref "HS1") (pin "1") (pinfunction "1_1") (pintype "passive+no_connect"))
    )
    (net (code "45") (name "unconnected-(IC1-Dis-Pad7)") (class "Default")
      (node (ref "IC1") (pin "7") (pinfunction "Dis_7") (pintype "passive+no_connect"))
    )
    (net (code "46") (name "unconnected-(IC2B-DNC-Pad8)") (class "Default")
      (node (ref "IC2") (pin "8") (pinfunction "DNC_8") (pintype "passive"))
    )
    (net (code "47") (name "unconnected-(IC2B-NULL-Pad1)") (class "Default")
      (node (ref "IC2") (pin "1") (pinfunction "NULL_1") (pintype "passive+no_connect"))
    )
    (net (code "48") (name "unconnected-(IC2B-NULL-Pad5)") (class "Default")
      (node (ref "IC2") (pin "5") (pinfunction "NULL_5") (pintype "passive+no_connect"))
    )
  )
)
